# MAIN.net
KiCad netlist of a schematic drawn in Altium Designer
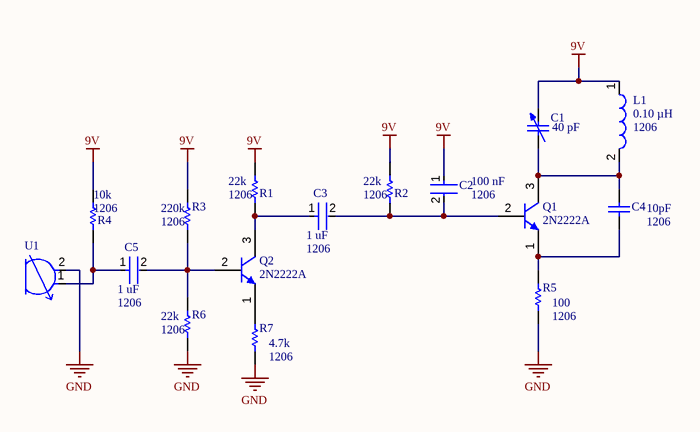
[diagram p0: MAIN.SchDoc]

(export (version "E")
  (design (tool "Eeschema 10.0.6"))
  (components
    (comp (ref "C1")
      (value "TZ03R300F169B00")
      (footprint "MURA-TZ03-2_V")
      (description "Variable Capacitor, Miniature Ceramic Trimmer, Green, 30 pF, -25 to 85 degC, 2-Pin THD, Bulk")
      (fields (field (name "MANUFACTURER") "Murata"))
      (libsource (lib "Altium Content Vault") (part "CAP-VAR-2"))
    )
    (comp (ref "C2")
      (value "100 nF")
      (footprint "FP-C1206C-EB-MFG")
      (description "CAP CER 10000PF 200V X7R 1206")
      (fields
        (field (name "OCTOPART") "https://octopart.com/c1206c103k2ractu-kemet-2299149")
        (field (name "MANUFACTURER") "KEMET")
        (field (name "PACKAGE") "1206")
      )
      (libsource (lib "Altium Content Vault") (part "b4654b650e69147ec39a6b967a45e02"))
    )
    (comp (ref "C3")
      (value "1 uF")
      (footprint "FP-CC1206-1_25-MFG")
      (description "CAP CER 0.1UF 50V X7R 1206")
      (fields
        (field (name "OCTOPART") "https://octopart.com/cc1206krx7r9bb104-yageo-39467816")
        (field (name "TOLERANCE") "0.1")
        (field (name "PACKAGE") "1206")
      )
      (libsource (lib "Altium Content Vault") (part "11868f565c42a9108669ba33697ecf6"))
    )
    (comp (ref "C4")
      (value "10pF")
      (footprint "CAPC1206(3216)170_M")
      (fields
        (field (name "TOLERANCE") "Â±0.25pF")
        (field (name "CASE-EIA") "1206")
        (field (name "Comment") "CAP 4.7pF 50V 1206(3216)")
      )
      (libsource (lib "Altium Content Vault") (part "CAP"))
    )
    (comp (ref "C5")
      (value "1 uF")
      (footprint "FP-CC1206-1_25-MFG")
      (description "CAP CER 0.1UF 50V X7R 1206")
      (fields
        (field (name "OCTOPART") "https://octopart.com/cc1206krx7r9bb104-yageo-39467816")
        (field (name "TOLERANCE") "0.1")
        (field (name "PACKAGE") "1206")
      )
      (libsource (lib "Altium Content Vault") (part "11868f565c42a9108669ba33697ecf6"))
    )
    (comp (ref "L1")
      (value "7447912")
      (footprint "SMD-1210")
      (description "SMD-Multilayer Inductor WE-MI, L = 0.10 µH")
      (fields (field (name "INDUCTANCE") "0.10 µH") (field (name "PACKAGEREFERENCE") "1206"))
      (libsource (lib "Altium Content Vault") (part "PAS-IND-INDUCTOR-2"))
    )
    (comp (ref "Q1")
      (value "2N2222A")
      (footprint "FAIR-TO-92")
      (description "NPN General-Purpose Amplifier, 40 V VCEO, 0.2 A, -55 to 150 degC, 2-Pin TO-92, RoHS, Bulk")
      (fields (field (name "MANUFACTURER") "FairchildSemiconductor"))
      (libsource (lib "Altium Content Vault") (part "NPN-E1B2C3-3"))
    )
    (comp (ref "Q2")
      (value "2N2222A")
      (footprint "FAIR-TO-92")
      (description "NPN General-Purpose Amplifier, 40 V VCEO, 0.2 A, -55 to 150 degC, 2-Pin TO-92, RoHS, Bulk")
      (fields (field (name "MANUFACTURER") "FairchildSemiconductor"))
      (libsource (lib "Altium Content Vault") (part "NPN-E1B2C3-3"))
    )
    (comp (ref "R1")
      (value "CRCW120610K0FKEAHP")
      (footprint "RESC3116X65X50NL20T20")
      (fields (field (name "MANUFACTURER") "Vishay Dale"))
      (libsource (lib "Altium Content Vault") (part "RES"))
    )
    (comp (ref "R2")
      (value "CRCW120610K0FKEAHP")
      (footprint "RESC3116X65X50NL20T20")
      (fields (field (name "MANUFACTURER") "Vishay Dale"))
      (libsource (lib "Altium Content Vault") (part "RES"))
    )
    (comp (ref "R3")
      (value "RT1206BRD071ML")
      (footprint "RESC3116X65X40ML10T20")
      (fields (field (name "MANUFACTURER") "Yageo"))
      (libsource (lib "Altium Content Vault") (part "RES"))
    )
    (comp (ref "R4")
      (value "CRCW120610K0FKEAHP")
      (footprint "RESC3116X65X50NL20T20")
      (fields (field (name "MANUFACTURER") "Vishay Dale"))
      (libsource (lib "Altium Content Vault") (part "RES"))
    )
    (comp (ref "R5")
      (value "ERJ-8ENF1001V")
      (footprint "RESC3216X70X50LL05T20")
      (fields (field (name "MANUFACTURER") "Panasonic"))
      (libsource (lib "Altium Content Vault") (part "RES"))
    )
    (comp (ref "R6")
      (value "CRCW1206100KFKEA")
      (footprint "RESC3216X60X45NL10T20")
      (fields (field (name "MANUFACTURER") "Vishay Dale"))
      (libsource (lib "Altium Content Vault") (part "RES"))
    )
    (comp (ref "R7")
      (value "ERJ-P08J101V")
      (footprint "RESC3216X70X50LL05T20")
      (fields (field (name "MANUFACTURER") "Panasonic"))
      (libsource (lib "Altium Content Vault") (part "RES"))
    )
    (comp (ref "U1")
      (value "POM-3535P-3-R")
      (footprint "FP-POM-3535P-3-R-MFG")
      (description "MIC COND ANALOG OMNI -35DB 6MM D")
      (libsource (lib "Altium Content Vault") (part "8932b53fa08aabe3022b5f676529f57"))
    )
  )
  (nets
    (net (code "1") (name "9V") (class "Default")
      (node (ref "C1") (pin "2") (pinfunction "2_2") (pintype "passive"))
      (node (ref "C2") (pin "1") (pinfunction "1_1") (pintype "passive"))
      (node (ref "L1") (pin "1") (pinfunction "1_1") (pintype "passive"))
      (node (ref "R1") (pin "2") (pinfunction "2_2") (pintype "passive"))
      (node (ref "R2") (pin "2") (pinfunction "2_2") (pintype "passive"))
      (node (ref "R3") (pin "2") (pinfunction "2_2") (pintype "passive"))
      (node (ref "R4") (pin "2") (pinfunction "2_2") (pintype "passive"))
    )
    (net (code "2") (name "GND") (class "Default")
      (node (ref "R5") (pin "1") (pinfunction "1_1") (pintype "passive"))
      (node (ref "R6") (pin "1") (pinfunction "1_1") (pintype "passive"))
      (node (ref "R7") (pin "1") (pinfunction "1_1") (pintype "passive"))
      (node (ref "U1") (pin "2") (pinfunction "C_2") (pintype "passive"))
    )
    (net (code "3") (name "Net-(Q1-B)") (class "Default")
      (node (ref "C2") (pin "2") (pinfunction "2_2") (pintype "passive"))
      (node (ref "C3") (pin "2") (pinfunction "2_2") (pintype "passive"))
      (node (ref "Q1") (pin "2") (pinfunction "B_2") (pintype "passive"))
      (node (ref "R2") (pin "1") (pinfunction "1_1") (pintype "passive"))
    )
    (net (code "4") (name "Net-(Q1-C)") (class "Default")
      (node (ref "C1") (pin "1") (pinfunction "1_1") (pintype "passive"))
      (node (ref "C4") (pin "2") (pinfunction "2_2") (pintype "passive"))
      (node (ref "L1") (pin "2") (pinfunction "2_2") (pintype "passive"))
      (node (ref "Q1") (pin "3") (pinfunction "C_3") (pintype "passive"))
    )
    (net (code "5") (name "Net-(Q1-E)") (class "Default")
      (node (ref "C4") (pin "1") (pinfunction "1_1") (pintype "passive"))
      (node (ref "Q1") (pin "1") (pinfunction "E_1") (pintype "passive"))
      (node (ref "R5") (pin "2") (pinfunction "2_2") (pintype "passive"))
    )
    (net (code "6") (name "Net-(Q2-B)") (class "Default")
      (node (ref "C5") (pin "2") (pinfunction "2_2") (pintype "passive"))
      (node (ref "Q2") (pin "2") (pinfunction "B_2") (pintype "passive"))
      (node (ref "R3") (pin "1") (pinfunction "1_1") (pintype "passive"))
      (node (ref "R6") (pin "2") (pinfunction "2_2") (pintype "passive"))
    )
    (net (code "7") (name "Net-(Q2-C)") (class "Default")
      (node (ref "C3") (pin "1") (pinfunction "1_1") (pintype "passive"))
      (node (ref "Q2") (pin "3") (pinfunction "C_3") (pintype "passive"))
      (node (ref "R1") (pin "1") (pinfunction "1_1") (pintype "passive"))
    )
    (net (code "8") (name "Net-(Q2-E)") (class "Default")
      (node (ref "Q2") (pin "1") (pinfunction "E_1") (pintype "passive"))
      (node (ref "R7") (pin "2") (pinfunction "2_2") (pintype "passive"))
    )
    (net (code "9") (name "Net-(U1-A)") (class "Default")
      (node (ref "C5") (pin "1") (pinfunction "1_1") (pintype "passive"))
      (node (ref "R4") (pin "1") (pinfunction "1_1") (pintype "passive"))
      (node (ref "U1") (pin "1") (pinfunction "A_1") (pintype "passive"))
    )
  )
)
